# LED_Controller_4Channels.net
KiCad netlist of a schematic drawn in Altium Designer
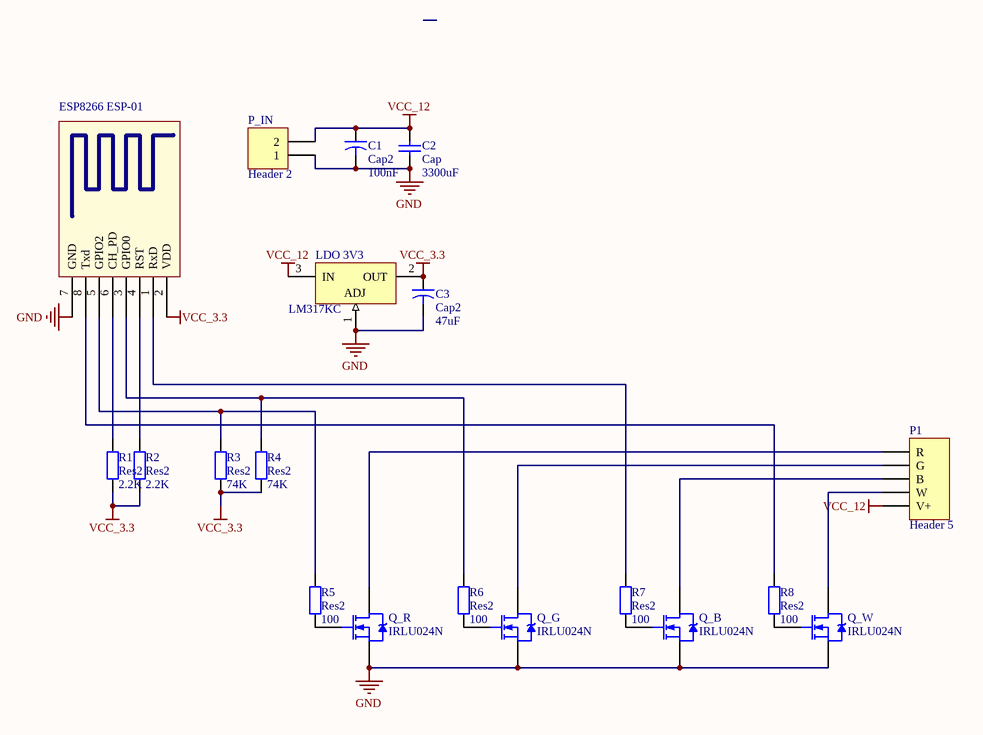
[diagram p0: LED_Controller_4Channels.SchDoc]

(export (version "E")
  (design (tool "Eeschema 10.0.6"))
  (components
    (comp (ref "C1")
      (value "Cap2")
      (footprint "CAPR5-4X5")
      (description "Capacitor")
      (fields (field (name "ALTIUM_VALUE") "100nF") (field (name "PUBLISHER") "Altium Limited"))
      (libsource (lib "Miscellaneous Devices") (part "Cap2"))
    )
    (comp (ref "C2")
      (value "Cap")
      (footprint "RAD-0.3")
      (description "Capacitor")
      (fields (field (name "ALTIUM_VALUE") "3300uF") (field (name "PUBLISHER") "Altium Limited"))
      (libsource (lib "Miscellaneous Devices") (part "Cap"))
    )
    (comp (ref "C3")
      (value "Cap2")
      (footprint "CAPR5-4X5")
      (description "Capacitor")
      (fields (field (name "ALTIUM_VALUE") "47uF") (field (name "PUBLISHER") "Altium Limited"))
      (libsource (lib "Miscellaneous Devices") (part "Cap2"))
    )
    (comp (ref "IC")
      (value "ESP8266 ESP-01")
      (footprint "ESP8266 ESP-01")
      (libsource (lib "cadLib") (part "ESP8266 ESP-01"))
    )
    (comp (ref "LDO 3V3")
      (value "LM317KC")
      (footprint "KC03")
      (description "3-Terminal Adjustable Regulator")
      (fields (field (name "PUBLISHER") "Altium Limited"))
      (libsource (lib "TI Power Mgt Voltage Regulator") (part "LM317KC"))
    )
    (comp (ref "P1")
      (value "Header 5")
      (footprint "HDR1X5")
      (description "Header, 5-Pin")
      (fields (field (name "PUBLISHER") "Altium Limited"))
      (libsource (lib "Miscellaneous Connectors") (part "Header 5"))
    )
    (comp (ref "P_IN")
      (value "Header 2")
      (footprint "HDR1X2")
      (description "Header, 2-Pin")
      (fields (field (name "PUBLISHER") "Altium Limited"))
      (libsource (lib "Miscellaneous Connectors") (part "Header 2"))
    )
    (comp (ref "Q_B")
      (value "IRLU024N")
      (footprint "D-Pack")
      (description "HEXFET Power MOSFET")
      (fields (field (name "PUBLISHER") "Altium Limited"))
      (libsource (lib "cadLib") (part "IRLU024N"))
    )
    (comp (ref "Q_G")
      (value "IRLU024N")
      (footprint "D-Pack")
      (description "HEXFET Power MOSFET")
      (fields (field (name "PUBLISHER") "Altium Limited"))
      (libsource (lib "cadLib") (part "IRLU024N"))
    )
    (comp (ref "Q_R")
      (value "IRLU024N")
      (footprint "D-Pack")
      (description "HEXFET Power MOSFET")
      (fields (field (name "PUBLISHER") "Altium Limited"))
      (libsource (lib "cadLib") (part "IRLU024N"))
    )
    (comp (ref "Q_W")
      (value "IRLU024N")
      (footprint "D-Pack")
      (description "HEXFET Power MOSFET")
      (fields (field (name "PUBLISHER") "Altium Limited"))
      (libsource (lib "cadLib") (part "IRLU024N"))
    )
    (comp (ref "R1")
      (value "Res2")
      (footprint "AXIAL-0.4")
      (description "Resistor")
      (fields (field (name "ALTIUM_VALUE") "2.2K") (field (name "PUBLISHER") "Altium Limited"))
      (libsource (lib "Miscellaneous Devices") (part "Res2"))
    )
    (comp (ref "R2")
      (value "Res2")
      (footprint "AXIAL-0.4")
      (description "Resistor")
      (fields (field (name "ALTIUM_VALUE") "2.2K") (field (name "PUBLISHER") "Altium Limited"))
      (libsource (lib "Miscellaneous Devices") (part "Res2"))
    )
    (comp (ref "R3")
      (value "Res2")
      (footprint "AXIAL-0.4")
      (description "Resistor")
      (fields (field (name "ALTIUM_VALUE") "74K") (field (name "PUBLISHER") "Altium Limited"))
      (libsource (lib "Miscellaneous Devices") (part "Res2"))
    )
    (comp (ref "R4")
      (value "Res2")
      (footprint "AXIAL-0.4")
      (description "Resistor")
      (fields (field (name "ALTIUM_VALUE") "74K") (field (name "PUBLISHER") "Altium Limited"))
      (libsource (lib "Miscellaneous Devices") (part "Res2"))
    )
    (comp (ref "R5")
      (value "Res2")
      (footprint "AXIAL-0.4")
      (description "Resistor")
      (fields (field (name "ALTIUM_VALUE") "100") (field (name "PUBLISHER") "Altium Limited"))
      (libsource (lib "Miscellaneous Devices") (part "Res2"))
    )
    (comp (ref "R6")
      (value "Res2")
      (footprint "AXIAL-0.4")
      (description "Resistor")
      (fields (field (name "ALTIUM_VALUE") "100") (field (name "PUBLISHER") "Altium Limited"))
      (libsource (lib "Miscellaneous Devices") (part "Res2"))
    )
    (comp (ref "R7")
      (value "Res2")
      (footprint "AXIAL-0.4")
      (description "Resistor")
      (fields (field (name "ALTIUM_VALUE") "100") (field (name "PUBLISHER") "Altium Limited"))
      (libsource (lib "Miscellaneous Devices") (part "Res2"))
    )
    (comp (ref "R8")
      (value "Res2")
      (footprint "AXIAL-0.4")
      (description "Resistor")
      (fields (field (name "ALTIUM_VALUE") "100") (field (name "PUBLISHER") "Altium Limited"))
      (libsource (lib "Miscellaneous Devices") (part "Res2"))
    )
  )
  (nets
    (net (code "1") (name "GND") (class "Default")
      (node (ref "C1") (pin "2") (pinfunction "2_2") (pintype "passive"))
      (node (ref "C2") (pin "1") (pinfunction "1_1") (pintype "passive"))
      (node (ref "C3") (pin "2") (pinfunction "2_2") (pintype "passive"))
      (node (ref "IC") (pin "7") (pinfunction "GND_7") (pintype "passive"))
      (node (ref "LDO 3V3") (pin "1") (pinfunction "ADJ_1") (pintype "input"))
      (node (ref "P_IN") (pin "1") (pinfunction "1_1") (pintype "passive"))
      (node (ref "Q_B") (pin "3") (pinfunction "S_3") (pintype "passive"))
      (node (ref "Q_G") (pin "3") (pinfunction "S_3") (pintype "passive"))
      (node (ref "Q_R") (pin "3") (pinfunction "S_3") (pintype "passive"))
      (node (ref "Q_W") (pin "3") (pinfunction "S_3") (pintype "passive"))
    )
    (net (code "2") (name "Net-(IC-CH_PD)") (class "Default")
      (node (ref "IC") (pin "6") (pinfunction "CH_PD_6") (pintype "passive"))
      (node (ref "R1") (pin "2") (pinfunction "2_2") (pintype "passive"))
    )
    (net (code "3") (name "Net-(IC-GPIO0)") (class "Default")
      (node (ref "IC") (pin "3") (pinfunction "GPIO0_3") (pintype "passive"))
      (node (ref "R4") (pin "2") (pinfunction "2_2") (pintype "passive"))
      (node (ref "R6") (pin "2") (pinfunction "2_2") (pintype "passive"))
    )
    (net (code "4") (name "Net-(IC-GPIO2)") (class "Default")
      (node (ref "IC") (pin "5") (pinfunction "GPIO2_5") (pintype "passive"))
      (node (ref "R3") (pin "2") (pinfunction "2_2") (pintype "passive"))
      (node (ref "R5") (pin "2") (pinfunction "2_2") (pintype "passive"))
    )
    (net (code "5") (name "Net-(IC-RST)") (class "Default")
      (node (ref "IC") (pin "4") (pinfunction "RST_4") (pintype "passive"))
      (node (ref "R2") (pin "2") (pinfunction "2_2") (pintype "passive"))
    )
    (net (code "6") (name "Net-(IC-RxD)") (class "Default")
      (node (ref "IC") (pin "1") (pinfunction "RxD_1") (pintype "passive"))
      (node (ref "R7") (pin "2") (pinfunction "2_2") (pintype "passive"))
    )
    (net (code "7") (name "Net-(IC-Txd)") (class "Default")
      (node (ref "IC") (pin "8") (pinfunction "Txd_8") (pintype "passive"))
      (node (ref "R8") (pin "2") (pinfunction "2_2") (pintype "passive"))
    )
    (net (code "8") (name "Net-(P1-B)") (class "Default")
      (node (ref "P1") (pin "3") (pinfunction "B_3") (pintype "passive"))
      (node (ref "Q_B") (pin "2") (pinfunction "D_2") (pintype "passive"))
    )
    (net (code "9") (name "Net-(P1-G)") (class "Default")
      (node (ref "P1") (pin "2") (pinfunction "G_2") (pintype "passive"))
      (node (ref "Q_G") (pin "2") (pinfunction "D_2") (pintype "passive"))
    )
    (net (code "10") (name "Net-(P1-R)") (class "Default")
      (node (ref "P1") (pin "1") (pinfunction "R_1") (pintype "passive"))
      (node (ref "Q_R") (pin "2") (pinfunction "D_2") (pintype "passive"))
    )
    (net (code "11") (name "Net-(P1-W)") (class "Default")
      (node (ref "P1") (pin "4") (pinfunction "W_4") (pintype "passive"))
      (node (ref "Q_W") (pin "2") (pinfunction "D_2") (pintype "passive"))
    )
    (net (code "12") (name "Net-(Q_B-G)") (class "Default")
      (node (ref "Q_B") (pin "1") (pinfunction "G_1") (pintype "passive"))
      (node (ref "R7") (pin "1") (pinfunction "1_1") (pintype "passive"))
    )
    (net (code "13") (name "Net-(Q_G-G)") (class "Default")
      (node (ref "Q_G") (pin "1") (pinfunction "G_1") (pintype "passive"))
      (node (ref "R6") (pin "1") (pinfunction "1_1") (pintype "passive"))
    )
    (net (code "14") (name "Net-(Q_R-G)") (class "Default")
      (node (ref "Q_R") (pin "1") (pinfunction "G_1") (pintype "passive"))
      (node (ref "R5") (pin "1") (pinfunction "1_1") (pintype "passive"))
    )
    (net (code "15") (name "Net-(Q_W-G)") (class "Default")
      (node (ref "Q_W") (pin "1") (pinfunction "G_1") (pintype "passive"))
      (node (ref "R8") (pin "1") (pinfunction "1_1") (pintype "passive"))
    )
    (net (code "16") (name "VCC_3.3") (class "Default")
      (node (ref "C3") (pin "1") (pinfunction "1_1") (pintype "passive"))
      (node (ref "IC") (pin "2") (pinfunction "VDD_2") (pintype "passive"))
      (node (ref "LDO 3V3") (pin "2") (pinfunction "OUT_2") (pintype "power_in"))
      (node (ref "R1") (pin "1") (pinfunction "1_1") (pintype "passive"))
      (node (ref "R2") (pin "1") (pinfunction "1_1") (pintype "passive"))
      (node (ref "R3") (pin "1") (pinfunction "1_1") (pintype "passive"))
      (node (ref "R4") (pin "1") (pinfunction "1_1") (pintype "passive"))
    )
    (net (code "17") (name "VCC_12") (class "Default")
      (node (ref "C1") (pin "1") (pinfunction "1_1") (pintype "passive"))
      (node (ref "C2") (pin "2") (pinfunction "2_2") (pintype "passive"))
      (node (ref "LDO 3V3") (pin "3") (pinfunction "IN_3") (pintype "power_in"))
      (node (ref "P1") (pin "5") (pinfunction "V+_5") (pintype "passive"))
      (node (ref "P_IN") (pin "2") (pinfunction "2_2") (pintype "passive"))
    )
  )
)
